# sensor.net
KiCad netlist of a schematic drawn in EAGLE
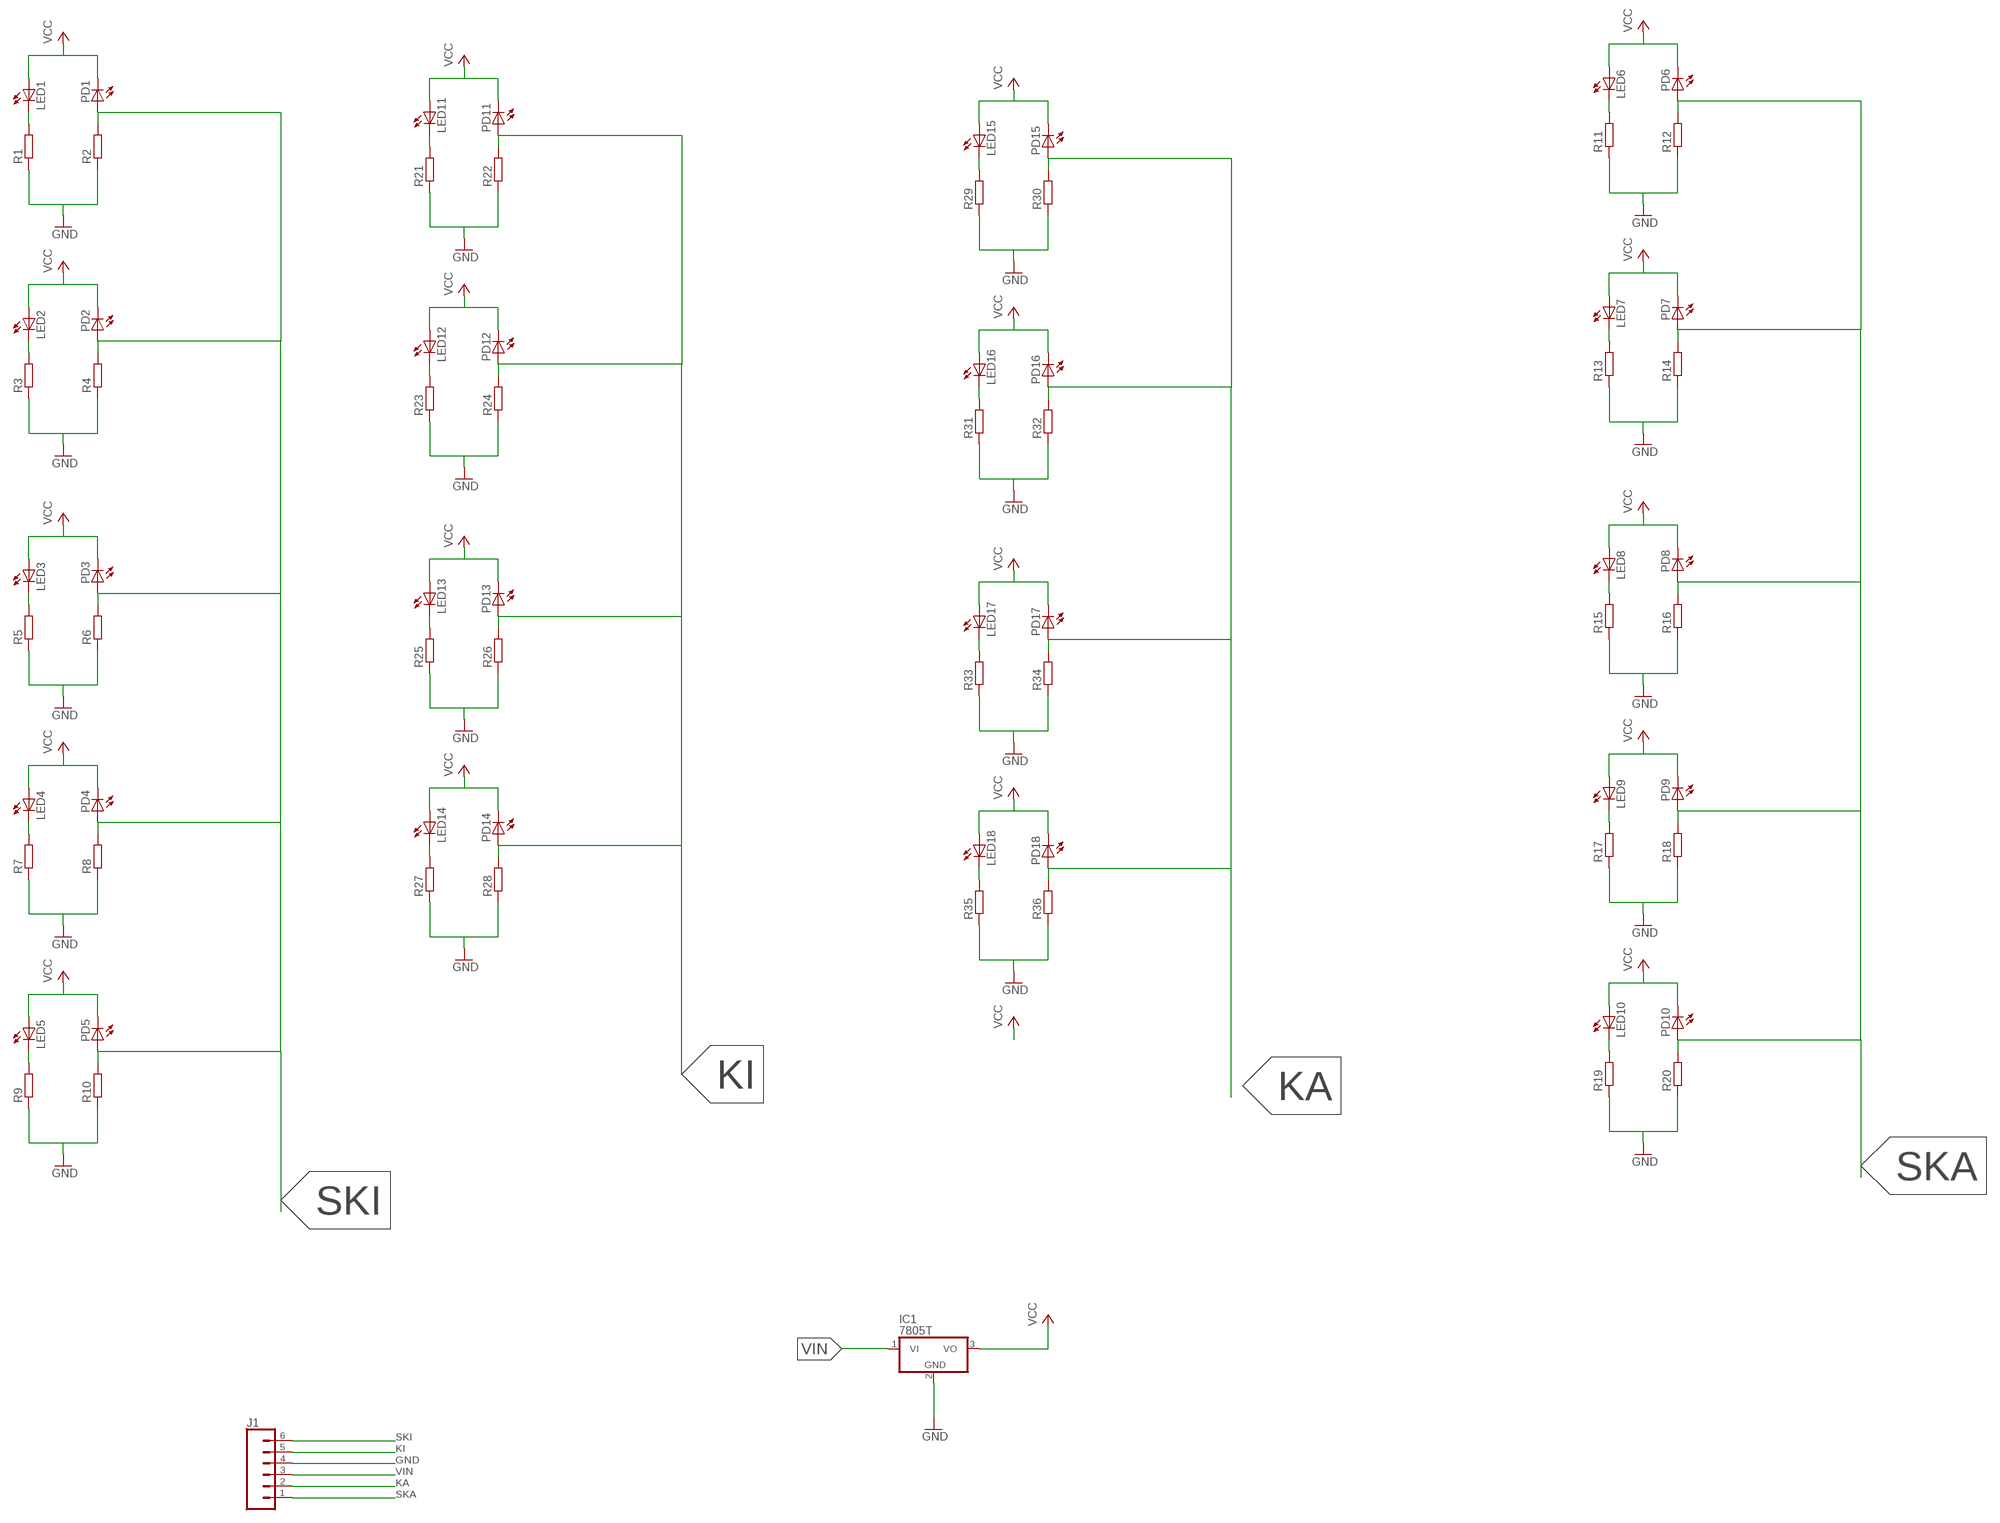
[diagram p0: schematic, sheet 1]

(export (version "E")
  (design (tool "Eeschema 10.0.6"))
  (components
    (comp (ref "IC1")
      (value "7805T")
      (footprint "eagle-import:TO220H")
      (libsource (lib "eagle-import") (part "78T05"))
    )
    (comp (ref "J1")
      (value "CONN_06LONGPADS")
      (footprint "eagle-import:1X06_LONGPADS")
      (libsource (lib "eagle-import") (part "CONN_06LONGPADS"))
    )
    (comp (ref "LED1")
      (value "LED5MM")
      (footprint "eagle-import:LED5MM")
      (libsource (lib "eagle-import") (part "LED5MM"))
    )
    (comp (ref "LED2")
      (value "LED5MM")
      (footprint "eagle-import:LED5MM")
      (libsource (lib "eagle-import") (part "LED5MM"))
    )
    (comp (ref "LED3")
      (value "LED5MM")
      (footprint "eagle-import:LED5MM")
      (libsource (lib "eagle-import") (part "LED5MM"))
    )
    (comp (ref "LED4")
      (value "LED5MM")
      (footprint "eagle-import:LED5MM")
      (libsource (lib "eagle-import") (part "LED5MM"))
    )
    (comp (ref "LED5")
      (value "LED5MM")
      (footprint "eagle-import:LED5MM")
      (libsource (lib "eagle-import") (part "LED5MM"))
    )
    (comp (ref "LED6")
      (value "LED5MM")
      (footprint "eagle-import:LED5MM")
      (libsource (lib "eagle-import") (part "LED5MM"))
    )
    (comp (ref "LED7")
      (value "LED5MM")
      (footprint "eagle-import:LED5MM")
      (libsource (lib "eagle-import") (part "LED5MM"))
    )
    (comp (ref "LED8")
      (value "LED5MM")
      (footprint "eagle-import:LED5MM")
      (libsource (lib "eagle-import") (part "LED5MM"))
    )
    (comp (ref "LED9")
      (value "LED5MM")
      (footprint "eagle-import:LED5MM")
      (libsource (lib "eagle-import") (part "LED5MM"))
    )
    (comp (ref "LED10")
      (value "LED5MM")
      (footprint "eagle-import:LED5MM")
      (libsource (lib "eagle-import") (part "LED5MM"))
    )
    (comp (ref "LED11")
      (value "LED5MM")
      (footprint "eagle-import:LED5MM")
      (libsource (lib "eagle-import") (part "LED5MM"))
    )
    (comp (ref "LED12")
      (value "LED5MM")
      (footprint "eagle-import:LED5MM")
      (libsource (lib "eagle-import") (part "LED5MM"))
    )
    (comp (ref "LED13")
      (value "LED5MM")
      (footprint "eagle-import:LED5MM")
      (libsource (lib "eagle-import") (part "LED5MM"))
    )
    (comp (ref "LED14")
      (value "LED5MM")
      (footprint "eagle-import:LED5MM")
      (libsource (lib "eagle-import") (part "LED5MM"))
    )
    (comp (ref "LED15")
      (value "LED5MM")
      (footprint "eagle-import:LED5MM")
      (libsource (lib "eagle-import") (part "LED5MM"))
    )
    (comp (ref "LED16")
      (value "LED5MM")
      (footprint "eagle-import:LED5MM")
      (libsource (lib "eagle-import") (part "LED5MM"))
    )
    (comp (ref "LED17")
      (value "LED5MM")
      (footprint "eagle-import:LED5MM")
      (libsource (lib "eagle-import") (part "LED5MM"))
    )
    (comp (ref "LED18")
      (value "LED5MM")
      (footprint "eagle-import:LED5MM")
      (libsource (lib "eagle-import") (part "LED5MM"))
    )
    (comp (ref "PD1")
      (value "LED3MM")
      (footprint "eagle-import:LED3MM")
      (libsource (lib "eagle-import") (part "LED3MM"))
    )
    (comp (ref "PD2")
      (value "LED3MM")
      (footprint "eagle-import:LED3MM")
      (libsource (lib "eagle-import") (part "LED3MM"))
    )
    (comp (ref "PD3")
      (value "LED3MM")
      (footprint "eagle-import:LED3MM")
      (libsource (lib "eagle-import") (part "LED3MM"))
    )
    (comp (ref "PD4")
      (value "LED3MM")
      (footprint "eagle-import:LED3MM")
      (libsource (lib "eagle-import") (part "LED3MM"))
    )
    (comp (ref "PD5")
      (value "LED3MM")
      (footprint "eagle-import:LED3MM")
      (libsource (lib "eagle-import") (part "LED3MM"))
    )
    (comp (ref "PD6")
      (value "LED3MM")
      (footprint "eagle-import:LED3MM")
      (libsource (lib "eagle-import") (part "LED3MM"))
    )
    (comp (ref "PD7")
      (value "LED3MM")
      (footprint "eagle-import:LED3MM")
      (libsource (lib "eagle-import") (part "LED3MM"))
    )
    (comp (ref "PD8")
      (value "LED3MM")
      (footprint "eagle-import:LED3MM")
      (libsource (lib "eagle-import") (part "LED3MM"))
    )
    (comp (ref "PD9")
      (value "LED3MM")
      (footprint "eagle-import:LED3MM")
      (libsource (lib "eagle-import") (part "LED3MM"))
    )
    (comp (ref "PD10")
      (value "LED3MM")
      (footprint "eagle-import:LED3MM")
      (libsource (lib "eagle-import") (part "LED3MM"))
    )
    (comp (ref "PD11")
      (value "LED3MM")
      (footprint "eagle-import:LED3MM")
      (libsource (lib "eagle-import") (part "LED3MM"))
    )
    (comp (ref "PD12")
      (value "LED3MM")
      (footprint "eagle-import:LED3MM")
      (libsource (lib "eagle-import") (part "LED3MM"))
    )
    (comp (ref "PD13")
      (value "LED3MM")
      (footprint "eagle-import:LED3MM")
      (libsource (lib "eagle-import") (part "LED3MM"))
    )
    (comp (ref "PD14")
      (value "LED3MM")
      (footprint "eagle-import:LED3MM")
      (libsource (lib "eagle-import") (part "LED3MM"))
    )
    (comp (ref "PD15")
      (value "LED3MM")
      (footprint "eagle-import:LED3MM")
      (libsource (lib "eagle-import") (part "LED3MM"))
    )
    (comp (ref "PD16")
      (value "LED3MM")
      (footprint "eagle-import:LED3MM")
      (libsource (lib "eagle-import") (part "LED3MM"))
    )
    (comp (ref "PD17")
      (value "LED3MM")
      (footprint "eagle-import:LED3MM")
      (libsource (lib "eagle-import") (part "LED3MM"))
    )
    (comp (ref "PD18")
      (value "LED3MM")
      (footprint "eagle-import:LED3MM")
      (libsource (lib "eagle-import") (part "LED3MM"))
    )
    (comp (ref "R1")
      (value "R-EU_0204/7")
      (footprint "eagle-import:0204_7")
      (libsource (lib "eagle-import") (part "R-EU_0204/7"))
    )
    (comp (ref "R2")
      (value "R-EU_0204/7")
      (footprint "eagle-import:0204_7")
      (libsource (lib "eagle-import") (part "R-EU_0204/7"))
    )
    (comp (ref "R3")
      (value "R-EU_0204/7")
      (footprint "eagle-import:0204_7")
      (libsource (lib "eagle-import") (part "R-EU_0204/7"))
    )
    (comp (ref "R4")
      (value "R-EU_0204/7")
      (footprint "eagle-import:0204_7")
      (libsource (lib "eagle-import") (part "R-EU_0204/7"))
    )
    (comp (ref "R5")
      (value "R-EU_0204/7")
      (footprint "eagle-import:0204_7")
      (libsource (lib "eagle-import") (part "R-EU_0204/7"))
    )
    (comp (ref "R6")
      (value "R-EU_0204/7")
      (footprint "eagle-import:0204_7")
      (libsource (lib "eagle-import") (part "R-EU_0204/7"))
    )
    (comp (ref "R7")
      (value "R-EU_0204/7")
      (footprint "eagle-import:0204_7")
      (libsource (lib "eagle-import") (part "R-EU_0204/7"))
    )
    (comp (ref "R8")
      (value "R-EU_0204/7")
      (footprint "eagle-import:0204_7")
      (libsource (lib "eagle-import") (part "R-EU_0204/7"))
    )
    (comp (ref "R9")
      (value "R-EU_0204/7")
      (footprint "eagle-import:0204_7")
      (libsource (lib "eagle-import") (part "R-EU_0204/7"))
    )
    (comp (ref "R10")
      (value "R-EU_0204/7")
      (footprint "eagle-import:0204_7")
      (libsource (lib "eagle-import") (part "R-EU_0204/7"))
    )
    (comp (ref "R11")
      (value "R-EU_0204/7")
      (footprint "eagle-import:0204_7")
      (libsource (lib "eagle-import") (part "R-EU_0204/7"))
    )
    (comp (ref "R12")
      (value "R-EU_0204/7")
      (footprint "eagle-import:0204_7")
      (libsource (lib "eagle-import") (part "R-EU_0204/7"))
    )
    (comp (ref "R13")
      (value "R-EU_0204/7")
      (footprint "eagle-import:0204_7")
      (libsource (lib "eagle-import") (part "R-EU_0204/7"))
    )
    (comp (ref "R14")
      (value "R-EU_0204/7")
      (footprint "eagle-import:0204_7")
      (libsource (lib "eagle-import") (part "R-EU_0204/7"))
    )
    (comp (ref "R15")
      (value "R-EU_0204/7")
      (footprint "eagle-import:0204_7")
      (libsource (lib "eagle-import") (part "R-EU_0204/7"))
    )
    (comp (ref "R16")
      (value "R-EU_0204/7")
      (footprint "eagle-import:0204_7")
      (libsource (lib "eagle-import") (part "R-EU_0204/7"))
    )
    (comp (ref "R17")
      (value "R-EU_0204/7")
      (footprint "eagle-import:0204_7")
      (libsource (lib "eagle-import") (part "R-EU_0204/7"))
    )
    (comp (ref "R18")
      (value "R-EU_0204/7")
      (footprint "eagle-import:0204_7")
      (libsource (lib "eagle-import") (part "R-EU_0204/7"))
    )
    (comp (ref "R19")
      (value "R-EU_0204/7")
      (footprint "eagle-import:0204_7")
      (libsource (lib "eagle-import") (part "R-EU_0204/7"))
    )
    (comp (ref "R20")
      (value "R-EU_0204/7")
      (footprint "eagle-import:0204_7")
      (libsource (lib "eagle-import") (part "R-EU_0204/7"))
    )
    (comp (ref "R21")
      (value "R-EU_0204/7")
      (footprint "eagle-import:0204_7")
      (libsource (lib "eagle-import") (part "R-EU_0204/7"))
    )
    (comp (ref "R22")
      (value "R-EU_0204/7")
      (footprint "eagle-import:0204_7")
      (libsource (lib "eagle-import") (part "R-EU_0204/7"))
    )
    (comp (ref "R23")
      (value "R-EU_0204/7")
      (footprint "eagle-import:0204_7")
      (libsource (lib "eagle-import") (part "R-EU_0204/7"))
    )
    (comp (ref "R24")
      (value "R-EU_0204/7")
      (footprint "eagle-import:0204_7")
      (libsource (lib "eagle-import") (part "R-EU_0204/7"))
    )
    (comp (ref "R25")
      (value "R-EU_0204/7")
      (footprint "eagle-import:0204_7")
      (libsource (lib "eagle-import") (part "R-EU_0204/7"))
    )
    (comp (ref "R26")
      (value "R-EU_0204/7")
      (footprint "eagle-import:0204_7")
      (libsource (lib "eagle-import") (part "R-EU_0204/7"))
    )
    (comp (ref "R27")
      (value "R-EU_0204/7")
      (footprint "eagle-import:0204_7")
      (libsource (lib "eagle-import") (part "R-EU_0204/7"))
    )
    (comp (ref "R28")
      (value "R-EU_0204/7")
      (footprint "eagle-import:0204_7")
      (libsource (lib "eagle-import") (part "R-EU_0204/7"))
    )
    (comp (ref "R29")
      (value "R-EU_0204/7")
      (footprint "eagle-import:0204_7")
      (libsource (lib "eagle-import") (part "R-EU_0204/7"))
    )
    (comp (ref "R30")
      (value "R-EU_0204/7")
      (footprint "eagle-import:0204_7")
      (libsource (lib "eagle-import") (part "R-EU_0204/7"))
    )
    (comp (ref "R31")
      (value "R-EU_0204/7")
      (footprint "eagle-import:0204_7")
      (libsource (lib "eagle-import") (part "R-EU_0204/7"))
    )
    (comp (ref "R32")
      (value "R-EU_0204/7")
      (footprint "eagle-import:0204_7")
      (libsource (lib "eagle-import") (part "R-EU_0204/7"))
    )
    (comp (ref "R33")
      (value "R-EU_0204/7")
      (footprint "eagle-import:0204_7")
      (libsource (lib "eagle-import") (part "R-EU_0204/7"))
    )
    (comp (ref "R34")
      (value "R-EU_0204/7")
      (footprint "eagle-import:0204_7")
      (libsource (lib "eagle-import") (part "R-EU_0204/7"))
    )
    (comp (ref "R35")
      (value "R-EU_0204/7")
      (footprint "eagle-import:0204_7")
      (libsource (lib "eagle-import") (part "R-EU_0204/7"))
    )
    (comp (ref "R36")
      (value "R-EU_0204/7")
      (footprint "eagle-import:0204_7")
      (libsource (lib "eagle-import") (part "R-EU_0204/7"))
    )
  )
  (nets
    (net (code "1") (name "GND") (class "Default")
      (node (ref "IC1") (pin "2") (pinfunction "GND_2") (pintype "passive"))
      (node (ref "J1") (pin "4") (pinfunction "4_4") (pintype "passive"))
      (node (ref "R1") (pin "1") (pinfunction "1_1") (pintype "passive"))
      (node (ref "R10") (pin "1") (pinfunction "1_1") (pintype "passive"))
      (node (ref "R11") (pin "1") (pinfunction "1_1") (pintype "passive"))
      (node (ref "R12") (pin "1") (pinfunction "1_1") (pintype "passive"))
      (node (ref "R13") (pin "1") (pinfunction "1_1") (pintype "passive"))
      (node (ref "R14") (pin "1") (pinfunction "1_1") (pintype "passive"))
      (node (ref "R15") (pin "1") (pinfunction "1_1") (pintype "passive"))
      (node (ref "R16") (pin "1") (pinfunction "1_1") (pintype "passive"))
      (node (ref "R17") (pin "1") (pinfunction "1_1") (pintype "passive"))
      (node (ref "R18") (pin "1") (pinfunction "1_1") (pintype "passive"))
      (node (ref "R19") (pin "1") (pinfunction "1_1") (pintype "passive"))
      (node (ref "R2") (pin "1") (pinfunction "1_1") (pintype "passive"))
      (node (ref "R20") (pin "1") (pinfunction "1_1") (pintype "passive"))
      (node (ref "R21") (pin "1") (pinfunction "1_1") (pintype "passive"))
      (node (ref "R22") (pin "1") (pinfunction "1_1") (pintype "passive"))
      (node (ref "R23") (pin "1") (pinfunction "1_1") (pintype "passive"))
      (node (ref "R24") (pin "1") (pinfunction "1_1") (pintype "passive"))
      (node (ref "R25") (pin "1") (pinfunction "1_1") (pintype "passive"))
      (node (ref "R26") (pin "1") (pinfunction "1_1") (pintype "passive"))
      (node (ref "R27") (pin "1") (pinfunction "1_1") (pintype "passive"))
      (node (ref "R28") (pin "1") (pinfunction "1_1") (pintype "passive"))
      (node (ref "R29") (pin "1") (pinfunction "1_1") (pintype "passive"))
      (node (ref "R3") (pin "1") (pinfunction "1_1") (pintype "passive"))
      (node (ref "R30") (pin "1") (pinfunction "1_1") (pintype "passive"))
      (node (ref "R31") (pin "1") (pinfunction "1_1") (pintype "passive"))
      (node (ref "R32") (pin "1") (pinfunction "1_1") (pintype "passive"))
      (node (ref "R33") (pin "1") (pinfunction "1_1") (pintype "passive"))
      (node (ref "R34") (pin "1") (pinfunction "1_1") (pintype "passive"))
      (node (ref "R35") (pin "1") (pinfunction "1_1") (pintype "passive"))
      (node (ref "R36") (pin "1") (pinfunction "1_1") (pintype "passive"))
      (node (ref "R4") (pin "1") (pinfunction "1_1") (pintype "passive"))
      (node (ref "R5") (pin "1") (pinfunction "1_1") (pintype "passive"))
      (node (ref "R6") (pin "1") (pinfunction "1_1") (pintype "passive"))
      (node (ref "R7") (pin "1") (pinfunction "1_1") (pintype "passive"))
      (node (ref "R8") (pin "1") (pinfunction "1_1") (pintype "passive"))
      (node (ref "R9") (pin "1") (pinfunction "1_1") (pintype "passive"))
    )
    (net (code "2") (name "KA") (class "Default")
      (node (ref "J1") (pin "2") (pinfunction "2_2") (pintype "passive"))
      (node (ref "PD15") (pin "A") (pinfunction "A_A") (pintype "passive"))
      (node (ref "PD16") (pin "A") (pinfunction "A_A") (pintype "passive"))
      (node (ref "PD17") (pin "A") (pinfunction "A_A") (pintype "passive"))
      (node (ref "PD18") (pin "A") (pinfunction "A_A") (pintype "passive"))
      (node (ref "R30") (pin "2") (pinfunction "2_2") (pintype "passive"))
      (node (ref "R32") (pin "2") (pinfunction "2_2") (pintype "passive"))
      (node (ref "R34") (pin "2") (pinfunction "2_2") (pintype "passive"))
      (node (ref "R36") (pin "2") (pinfunction "2_2") (pintype "passive"))
    )
    (net (code "3") (name "KI") (class "Default")
      (node (ref "J1") (pin "5") (pinfunction "5_5") (pintype "passive"))
      (node (ref "PD11") (pin "A") (pinfunction "A_A") (pintype "passive"))
      (node (ref "PD12") (pin "A") (pinfunction "A_A") (pintype "passive"))
      (node (ref "PD13") (pin "A") (pinfunction "A_A") (pintype "passive"))
      (node (ref "PD14") (pin "A") (pinfunction "A_A") (pintype "passive"))
      (node (ref "R22") (pin "2") (pinfunction "2_2") (pintype "passive"))
      (node (ref "R24") (pin "2") (pinfunction "2_2") (pintype "passive"))
      (node (ref "R26") (pin "2") (pinfunction "2_2") (pintype "passive"))
      (node (ref "R28") (pin "2") (pinfunction "2_2") (pintype "passive"))
    )
    (net (code "4") (name "Net-(LED1-C)") (class "Default")
      (node (ref "LED1") (pin "K") (pinfunction "C_K") (pintype "passive"))
      (node (ref "R1") (pin "2") (pinfunction "2_2") (pintype "passive"))
    )
    (net (code "5") (name "Net-(LED2-C)") (class "Default")
      (node (ref "LED2") (pin "K") (pinfunction "C_K") (pintype "passive"))
      (node (ref "R3") (pin "2") (pinfunction "2_2") (pintype "passive"))
    )
    (net (code "6") (name "Net-(LED3-C)") (class "Default")
      (node (ref "LED3") (pin "K") (pinfunction "C_K") (pintype "passive"))
      (node (ref "R5") (pin "2") (pinfunction "2_2") (pintype "passive"))
    )
    (net (code "7") (name "Net-(LED4-C)") (class "Default")
      (node (ref "LED4") (pin "K") (pinfunction "C_K") (pintype "passive"))
      (node (ref "R7") (pin "2") (pinfunction "2_2") (pintype "passive"))
    )
    (net (code "8") (name "Net-(LED5-C)") (class "Default")
      (node (ref "LED5") (pin "K") (pinfunction "C_K") (pintype "passive"))
      (node (ref "R9") (pin "2") (pinfunction "2_2") (pintype "passive"))
    )
    (net (code "9") (name "Net-(LED6-C)") (class "Default")
      (node (ref "LED6") (pin "K") (pinfunction "C_K") (pintype "passive"))
      (node (ref "R11") (pin "2") (pinfunction "2_2") (pintype "passive"))
    )
    (net (code "10") (name "Net-(LED7-C)") (class "Default")
      (node (ref "LED7") (pin "K") (pinfunction "C_K") (pintype "passive"))
      (node (ref "R13") (pin "2") (pinfunction "2_2") (pintype "passive"))
    )
    (net (code "11") (name "Net-(LED8-C)") (class "Default")
      (node (ref "LED8") (pin "K") (pinfunction "C_K") (pintype "passive"))
      (node (ref "R15") (pin "2") (pinfunction "2_2") (pintype "passive"))
    )
    (net (code "12") (name "Net-(LED9-C)") (class "Default")
      (node (ref "LED9") (pin "K") (pinfunction "C_K") (pintype "passive"))
      (node (ref "R17") (pin "2") (pinfunction "2_2") (pintype "passive"))
    )
    (net (code "13") (name "Net-(LED10-C)") (class "Default")
      (node (ref "LED10") (pin "K") (pinfunction "C_K") (pintype "passive"))
      (node (ref "R19") (pin "2") (pinfunction "2_2") (pintype "passive"))
    )
    (net (code "14") (name "Net-(LED11-C)") (class "Default")
      (node (ref "LED11") (pin "K") (pinfunction "C_K") (pintype "passive"))
      (node (ref "R21") (pin "2") (pinfunction "2_2") (pintype "passive"))
    )
    (net (code "15") (name "Net-(LED12-C)") (class "Default")
      (node (ref "LED12") (pin "K") (pinfunction "C_K") (pintype "passive"))
      (node (ref "R23") (pin "2") (pinfunction "2_2") (pintype "passive"))
    )
    (net (code "16") (name "Net-(LED13-C)") (class "Default")
      (node (ref "LED13") (pin "K") (pinfunction "C_K") (pintype "passive"))
      (node (ref "R25") (pin "2") (pinfunction "2_2") (pintype "passive"))
    )
    (net (code "17") (name "Net-(LED14-C)") (class "Default")
      (node (ref "LED14") (pin "K") (pinfunction "C_K") (pintype "passive"))
      (node (ref "R27") (pin "2") (pinfunction "2_2") (pintype "passive"))
    )
    (net (code "18") (name "Net-(LED15-C)") (class "Default")
      (node (ref "LED15") (pin "K") (pinfunction "C_K") (pintype "passive"))
      (node (ref "R29") (pin "2") (pinfunction "2_2") (pintype "passive"))
    )
    (net (code "19") (name "Net-(LED16-C)") (class "Default")
      (node (ref "LED16") (pin "K") (pinfunction "C_K") (pintype "passive"))
      (node (ref "R31") (pin "2") (pinfunction "2_2") (pintype "passive"))
    )
    (net (code "20") (name "Net-(LED17-C)") (class "Default")
      (node (ref "LED17") (pin "K") (pinfunction "C_K") (pintype "passive"))
      (node (ref "R33") (pin "2") (pinfunction "2_2") (pintype "passive"))
    )
    (net (code "21") (name "Net-(LED18-C)") (class "Default")
      (node (ref "LED18") (pin "K") (pinfunction "C_K") (pintype "passive"))
      (node (ref "R35") (pin "2") (pinfunction "2_2") (pintype "passive"))
    )
    (net (code "22") (name "SKA") (class "Default")
      (node (ref "J1") (pin "1") (pinfunction "1_1") (pintype "passive"))
      (node (ref "PD10") (pin "A") (pinfunction "A_A") (pintype "passive"))
      (node (ref "PD6") (pin "A") (pinfunction "A_A") (pintype "passive"))
      (node (ref "PD7") (pin "A") (pinfunction "A_A") (pintype "passive"))
      (node (ref "PD8") (pin "A") (pinfunction "A_A") (pintype "passive"))
      (node (ref "PD9") (pin "A") (pinfunction "A_A") (pintype "passive"))
      (node (ref "R12") (pin "2") (pinfunction "2_2") (pintype "passive"))
      (node (ref "R14") (pin "2") (pinfunction "2_2") (pintype "passive"))
      (node (ref "R16") (pin "2") (pinfunction "2_2") (pintype "passive"))
      (node (ref "R18") (pin "2") (pinfunction "2_2") (pintype "passive"))
      (node (ref "R20") (pin "2") (pinfunction "2_2") (pintype "passive"))
    )
    (net (code "23") (name "SKI") (class "Default")
      (node (ref "J1") (pin "6") (pinfunction "6_6") (pintype "passive"))
      (node (ref "PD1") (pin "A") (pinfunction "A_A") (pintype "passive"))
      (node (ref "PD2") (pin "A") (pinfunction "A_A") (pintype "passive"))
      (node (ref "PD3") (pin "A") (pinfunction "A_A") (pintype "passive"))
      (node (ref "PD4") (pin "A") (pinfunction "A_A") (pintype "passive"))
      (node (ref "PD5") (pin "A") (pinfunction "A_A") (pintype "passive"))
      (node (ref "R10") (pin "2") (pinfunction "2_2") (pintype "passive"))
      (node (ref "R2") (pin "2") (pinfunction "2_2") (pintype "passive"))
      (node (ref "R4") (pin "2") (pinfunction "2_2") (pintype "passive"))
      (node (ref "R6") (pin "2") (pinfunction "2_2") (pintype "passive"))
      (node (ref "R8") (pin "2") (pinfunction "2_2") (pintype "passive"))
    )
    (net (code "24") (name "VCC") (class "Default")
      (node (ref "IC1") (pin "3") (pinfunction "VO_3") (pintype "passive"))
      (node (ref "LED1") (pin "A") (pinfunction "A_A") (pintype "passive"))
      (node (ref "LED10") (pin "A") (pinfunction "A_A") (pintype "passive"))
      (node (ref "LED11") (pin "A") (pinfunction "A_A") (pintype "passive"))
      (node (ref "LED12") (pin "A") (pinfunction "A_A") (pintype "passive"))
      (node (ref "LED13") (pin "A") (pinfunction "A_A") (pintype "passive"))
      (node (ref "LED14") (pin "A") (pinfunction "A_A") (pintype "passive"))
      (node (ref "LED15") (pin "A") (pinfunction "A_A") (pintype "passive"))
      (node (ref "LED16") (pin "A") (pinfunction "A_A") (pintype "passive"))
      (node (ref "LED17") (pin "A") (pinfunction "A_A") (pintype "passive"))
      (node (ref "LED18") (pin "A") (pinfunction "A_A") (pintype "passive"))
      (node (ref "LED2") (pin "A") (pinfunction "A_A") (pintype "passive"))
      (node (ref "LED3") (pin "A") (pinfunction "A_A") (pintype "passive"))
      (node (ref "LED4") (pin "A") (pinfunction "A_A") (pintype "passive"))
      (node (ref "LED5") (pin "A") (pinfunction "A_A") (pintype "passive"))
      (node (ref "LED6") (pin "A") (pinfunction "A_A") (pintype "passive"))
      (node (ref "LED7") (pin "A") (pinfunction "A_A") (pintype "passive"))
      (node (ref "LED8") (pin "A") (pinfunction "A_A") (pintype "passive"))
      (node (ref "LED9") (pin "A") (pinfunction "A_A") (pintype "passive"))
      (node (ref "PD1") (pin "K") (pinfunction "C_K") (pintype "passive"))
      (node (ref "PD10") (pin "K") (pinfunction "C_K") (pintype "passive"))
      (node (ref "PD11") (pin "K") (pinfunction "C_K") (pintype "passive"))
      (node (ref "PD12") (pin "K") (pinfunction "C_K") (pintype "passive"))
      (node (ref "PD13") (pin "K") (pinfunction "C_K") (pintype "passive"))
      (node (ref "PD14") (pin "K") (pinfunction "C_K") (pintype "passive"))
      (node (ref "PD15") (pin "K") (pinfunction "C_K") (pintype "passive"))
      (node (ref "PD16") (pin "K") (pinfunction "C_K") (pintype "passive"))
      (node (ref "PD17") (pin "K") (pinfunction "C_K") (pintype "passive"))
      (node (ref "PD18") (pin "K") (pinfunction "C_K") (pintype "passive"))
      (node (ref "PD2") (pin "K") (pinfunction "C_K") (pintype "passive"))
      (node (ref "PD3") (pin "K") (pinfunction "C_K") (pintype "passive"))
      (node (ref "PD4") (pin "K") (pinfunction "C_K") (pintype "passive"))
      (node (ref "PD5") (pin "K") (pinfunction "C_K") (pintype "passive"))
      (node (ref "PD6") (pin "K") (pinfunction "C_K") (pintype "passive"))
      (node (ref "PD7") (pin "K") (pinfunction "C_K") (pintype "passive"))
      (node (ref "PD8") (pin "K") (pinfunction "C_K") (pintype "passive"))
      (node (ref "PD9") (pin "K") (pinfunction "C_K") (pintype "passive"))
    )
    (net (code "25") (name "VIN") (class "Default")
      (node (ref "IC1") (pin "1") (pinfunction "VI_1") (pintype "input"))
      (node (ref "J1") (pin "3") (pinfunction "3_3") (pintype "passive"))
    )
  )
)
